# design.net
KiCad netlist of a schematic drawn in Altium Designer
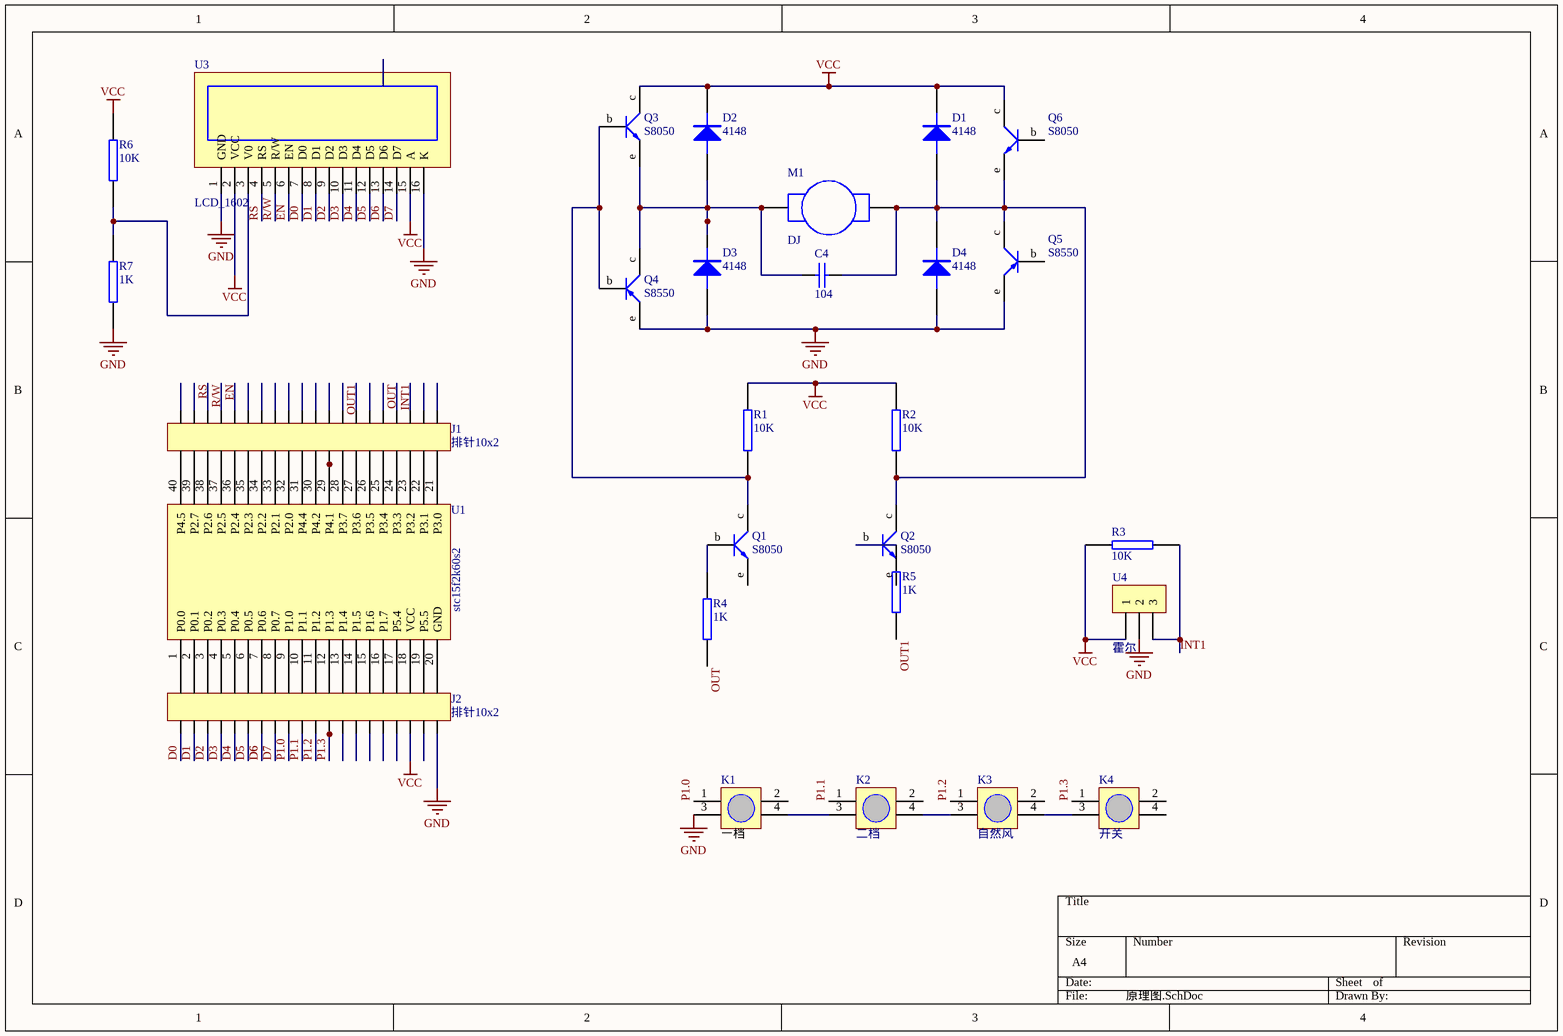
[diagram p0: 原理图.SchDoc]

(export (version "E")
  (design (tool "Eeschema 10.0.6"))
  (components
    (comp (ref "C4")
      (value "104")
      (footprint "C01")
      (description "Capacitor")
      (libsource (lib "altium-import") (part "root_1_CAP_"))
    )
    (comp (ref "D1")
      (value "4148")
      (footprint "DIODE0.2")
      (description "Diode")
      (libsource (lib "altium-import") (part "root_1_DIODE_"))
    )
    (comp (ref "D2")
      (value "4148")
      (footprint "DIODE0.2")
      (description "Diode")
      (libsource (lib "altium-import") (part "root_1_DIODE_"))
    )
    (comp (ref "D3")
      (value "4148")
      (footprint "DIODE0.2")
      (description "Diode")
      (libsource (lib "altium-import") (part "root_1_DIODE_"))
    )
    (comp (ref "D4")
      (value "4148")
      (footprint "DIODE0.2")
      (description "Diode")
      (libsource (lib "altium-import") (part "root_1_DIODE_"))
    )
    (comp (ref "J1") (value "排针10x2") (libsource (lib "原理图库") (part "排针10x2")))
    (comp (ref "J2") (value "排针10x2") (libsource (lib "原理图库") (part "排针10x2")))
    (comp (ref "K1") (value "一档") (footprint "KEY") (libsource (lib "altium-import") (part "root_0_KEY_")))
    (comp (ref "K2") (value "二档") (footprint "KEY") (libsource (lib "altium-import") (part "root_0_KEY_")))
    (comp (ref "K3") (value "自然风") (footprint "KEY") (libsource (lib "altium-import") (part "root_0_KEY_")))
    (comp (ref "K4") (value "开关") (footprint "KEY") (libsource (lib "altium-import") (part "root_0_KEY_")))
    (comp (ref "M1")
      (value "DJ")
      (footprint "SIP2")
      (libsource (lib "altium-import") (part "root_1_MOTOR AC_"))
    )
    (comp (ref "Q1") (value "S8050") (footprint "PNP") (libsource (lib "altium-import") (part "root_0_NPN_")))
    (comp (ref "Q2") (value "S8050") (footprint "PNP") (libsource (lib "altium-import") (part "root_0_NPN_")))
    (comp (ref "Q3") (value "S8050") (footprint "PNP") (libsource (lib "altium-import") (part "root_0_NPN_")))
    (comp (ref "Q4") (value "S8550") (footprint "PNP") (libsource (lib "altium-import") (part "root_0_PNP_")))
    (comp (ref "Q5")
      (value "S8550")
      (footprint "PNP")
      (libsource (lib "altium-import") (part "root_0_mirrored_PNP_"))
    )
    (comp (ref "Q6")
      (value "S8050")
      (footprint "PNP")
      (libsource (lib "altium-import") (part "root_0_mirrored_NPN_"))
    )
    (comp (ref "R1")
      (value "10K")
      (footprint "R-DIP")
      (libsource (lib "altium-import") (part "root_3_RES2_"))
    )
    (comp (ref "R2")
      (value "10K")
      (footprint "R-DIP")
      (libsource (lib "altium-import") (part "root_3_RES2_"))
    )
    (comp (ref "R3")
      (value "10K")
      (footprint "R-DIP")
      (libsource (lib "altium-import") (part "root_0_RES2_"))
    )
    (comp (ref "R4") (value "1K") (footprint "R-DIP") (libsource (lib "altium-import") (part "root_3_RES2_")))
    (comp (ref "R5") (value "1K") (footprint "R-DIP") (libsource (lib "altium-import") (part "root_3_RES2_")))
    (comp (ref "R6")
      (value "10K")
      (footprint "R-DIP")
      (libsource (lib "altium-import") (part "root_3_RES2_"))
    )
    (comp (ref "R7") (value "1K") (footprint "R-DIP") (libsource (lib "altium-import") (part "root_3_RES2_")))
    (comp (ref "U1") (value "stc15f2k60s2") (libsource (lib "altium-import") (part "root_1_STC15F2K60S2_")))
    (comp (ref "U3")
      (value "LCD_1602")
      (footprint "SIP16")
      (libsource (lib "altium-import") (part "root_0_mirrored_LCM1602_"))
    )
    (comp (ref "U4")
      (value "霍尔")
      (footprint "SIP3")
      (description "Connector")
      (libsource (lib "altium-import") (part "root_1_CON3_"))
    )
  )
  (nets
    (net (code "1") (name "/D0") (class "Default")
      (node (ref "J2") (pin "1") (pinfunction "1_1") (pintype "passive"))
      (node (ref "U3") (pin "7") (pinfunction "D0_7") (pintype "passive"))
    )
    (net (code "2") (name "/D1") (class "Default")
      (node (ref "J2") (pin "2") (pinfunction "2_2") (pintype "passive"))
      (node (ref "U3") (pin "8") (pinfunction "D1_8") (pintype "passive"))
    )
    (net (code "3") (name "/D2") (class "Default")
      (node (ref "J2") (pin "2") (pinfunction "2_2") (pintype "passive"))
      (node (ref "U3") (pin "9") (pinfunction "D2_9") (pintype "passive"))
    )
    (net (code "4") (name "/D3") (class "Default")
      (node (ref "J2") (pin "2") (pinfunction "2_2") (pintype "passive"))
      (node (ref "U3") (pin "10") (pinfunction "D3_10") (pintype "passive"))
    )
    (net (code "5") (name "/D4") (class "Default")
      (node (ref "J2") (pin "2") (pinfunction "2_2") (pintype "passive"))
      (node (ref "U3") (pin "11") (pinfunction "D4_11") (pintype "passive"))
    )
    (net (code "6") (name "/D5") (class "Default")
      (node (ref "J2") (pin "2") (pinfunction "2_2") (pintype "passive"))
      (node (ref "U3") (pin "12") (pinfunction "D5_12") (pintype "passive"))
    )
    (net (code "7") (name "/D6") (class "Default")
      (node (ref "J2") (pin "1") (pinfunction "1_1") (pintype "passive"))
      (node (ref "U3") (pin "13") (pinfunction "D6_13") (pintype "passive"))
    )
    (net (code "8") (name "/D7") (class "Default")
      (node (ref "J2") (pin "2") (pinfunction "2_2") (pintype "passive"))
      (node (ref "U3") (pin "14") (pinfunction "D7_14") (pintype "passive"))
    )
    (net (code "9") (name "/EN") (class "Default")
      (node (ref "J1") (pin "3") (pinfunction "3_3") (pintype "passive"))
      (node (ref "U3") (pin "6") (pinfunction "EN_6") (pintype "passive"))
    )
    (net (code "10") (name "/INT1") (class "Default")
      (node (ref "J1") (pin "3") (pinfunction "3_3") (pintype "passive"))
      (node (ref "R3") (pin "2") (pinfunction "2_2") (pintype "passive"))
      (node (ref "U4") (pin "3") (pinfunction "3_3") (pintype "passive"))
    )
    (net (code "11") (name "/OUT") (class "Default")
      (node (ref "J1") (pin "3") (pinfunction "3_3") (pintype "passive"))
      (node (ref "R4") (pin "2") (pinfunction "2_2") (pintype "passive"))
    )
    (net (code "12") (name "/OUT1") (class "Default")
      (node (ref "J1") (pin "2") (pinfunction "2_2") (pintype "passive"))
      (node (ref "R5") (pin "2") (pinfunction "2_2") (pintype "passive"))
    )
    (net (code "13") (name "/P1.0") (class "Default")
      (node (ref "J2") (pin "2") (pinfunction "2_2") (pintype "passive"))
      (node (ref "K1") (pin "1") (pintype "passive"))
    )
    (net (code "14") (name "/P1.1") (class "Default")
      (node (ref "J2") (pin "2") (pinfunction "2_2") (pintype "passive"))
      (node (ref "K2") (pin "1") (pintype "passive"))
    )
    (net (code "15") (name "/P1.2") (class "Default")
      (node (ref "J2") (pin "2") (pinfunction "2_2") (pintype "passive"))
      (node (ref "K3") (pin "1") (pintype "passive"))
    )
    (net (code "16") (name "/P1.3") (class "Default")
      (node (ref "J2") (pin "1") (pinfunction "1_1") (pintype "passive"))
      (node (ref "J2") (pin "2") (pinfunction "2_2") (pintype "passive"))
      (node (ref "K4") (pin "1") (pintype "passive"))
    )
    (net (code "17") (name "/RS") (class "Default")
      (node (ref "J1") (pin "3") (pinfunction "3_3") (pintype "passive"))
      (node (ref "U3") (pin "4") (pinfunction "RS_4") (pintype "passive"))
    )
    (net (code "18") (name "/R{slash}W") (class "Default")
      (node (ref "J1") (pin "2") (pinfunction "2_2") (pintype "passive"))
      (node (ref "U3") (pin "5") (pinfunction "R/W_5") (pintype "passive"))
    )
    (net (code "19") (name "GND") (class "Default")
      (node (ref "D3") (pin "1") (pinfunction "A_1") (pintype "passive"))
      (node (ref "D4") (pin "1") (pinfunction "A_1") (pintype "passive"))
      (node (ref "J2") (pin "2") (pinfunction "2_2") (pintype "passive"))
      (node (ref "K1") (pin "3") (pintype "passive"))
      (node (ref "Q4") (pin "e") (pintype "passive"))
      (node (ref "Q5") (pin "e") (pintype "passive"))
      (node (ref "R7") (pin "2") (pinfunction "2_2") (pintype "passive"))
      (node (ref "U3") (pin "1") (pinfunction "GND_1") (pintype "passive"))
      (node (ref "U3") (pin "16") (pinfunction "K_16") (pintype "passive"))
      (node (ref "U4") (pin "2") (pinfunction "2_2") (pintype "passive"))
    )
    (net (code "20") (name "Net-(D1-A)") (class "Default")
      (node (ref "C4") (pin "2") (pinfunction "2_2") (pintype "passive"))
      (node (ref "D1") (pin "1") (pinfunction "A_1") (pintype "passive"))
      (node (ref "D4") (pin "2") (pinfunction "K_2") (pintype "passive"))
      (node (ref "M1") (pin "2") (pinfunction "2_2") (pintype "passive"))
      (node (ref "Q2") (pin "c") (pintype "passive"))
      (node (ref "Q5") (pin "c") (pintype "passive"))
      (node (ref "Q6") (pin "e") (pintype "passive"))
      (node (ref "R2") (pin "2") (pinfunction "2_2") (pintype "passive"))
    )
    (net (code "21") (name "Net-(D2-A)") (class "Default")
      (node (ref "C4") (pin "1") (pinfunction "1_1") (pintype "passive"))
      (node (ref "D2") (pin "1") (pinfunction "A_1") (pintype "passive"))
      (node (ref "D3") (pin "2") (pinfunction "K_2") (pintype "passive"))
      (node (ref "M1") (pin "1") (pinfunction "1_1") (pintype "passive"))
      (node (ref "Q3") (pin "e") (pintype "passive"))
      (node (ref "Q4") (pin "c") (pintype "passive"))
    )
    (net (code "22") (name "Net-(K1-Pad4)") (class "Default")
      (node (ref "K1") (pin "4") (pintype "passive"))
      (node (ref "K2") (pin "3") (pintype "passive"))
    )
    (net (code "23") (name "Net-(K2-Pad4)") (class "Default")
      (node (ref "K2") (pin "4") (pintype "passive"))
      (node (ref "K3") (pin "3") (pintype "passive"))
    )
    (net (code "24") (name "Net-(K3-Pad4)") (class "Default")
      (node (ref "K3") (pin "4") (pintype "passive"))
      (node (ref "K4") (pin "3") (pintype "passive"))
    )
    (net (code "25") (name "Net-(Q1-Padb)") (class "Default")
      (node (ref "Q1") (pin "b") (pintype "passive"))
      (node (ref "R4") (pin "1") (pinfunction "1_1") (pintype "passive"))
    )
    (net (code "26") (name "Net-(Q1-Padc)") (class "Default")
      (node (ref "Q1") (pin "c") (pintype "passive"))
      (node (ref "Q3") (pin "b") (pintype "passive"))
      (node (ref "Q4") (pin "b") (pintype "passive"))
      (node (ref "R1") (pin "2") (pinfunction "2_2") (pintype "passive"))
    )
    (net (code "27") (name "Net-(Q2-Padb)") (class "Default")
      (node (ref "Q2") (pin "b") (pintype "passive"))
      (node (ref "R5") (pin "1") (pinfunction "1_1") (pintype "passive"))
    )
    (net (code "28") (name "Net-(U1-GND)") (class "Default")
      (node (ref "J2") (pin "2") (pinfunction "2_2") (pintype "passive"))
      (node (ref "U1") (pin "20") (pinfunction "GND_20") (pintype "passive"))
    )
    (net (code "29") (name "Net-(U1-P0.0)") (class "Default")
      (node (ref "J2") (pin "2") (pinfunction "2_2") (pintype "passive"))
      (node (ref "U1") (pin "1") (pinfunction "P0.0_1") (pintype "passive"))
    )
    (net (code "30") (name "Net-(U1-P0.1)") (class "Default")
      (node (ref "J2") (pin "3") (pinfunction "3_3") (pintype "passive"))
      (node (ref "U1") (pin "2") (pinfunction "P0.1_2") (pintype "passive"))
    )
    (net (code "31") (name "Net-(U1-P0.2)") (class "Default")
      (node (ref "J2") (pin "2") (pinfunction "2_2") (pintype "passive"))
      (node (ref "U1") (pin "3") (pinfunction "P0.2_3") (pintype "passive"))
    )
    (net (code "32") (name "Net-(U1-P0.3)") (class "Default")
      (node (ref "J2") (pin "3") (pinfunction "3_3") (pintype "passive"))
      (node (ref "U1") (pin "4") (pinfunction "P0.3_4") (pintype "passive"))
    )
    (net (code "33") (name "Net-(U1-P0.4)") (class "Default")
      (node (ref "J2") (pin "2") (pinfunction "2_2") (pintype "passive"))
      (node (ref "U1") (pin "5") (pinfunction "P0.4_5") (pintype "passive"))
    )
    (net (code "34") (name "Net-(U1-P0.5)") (class "Default")
      (node (ref "J2") (pin "3") (pinfunction "3_3") (pintype "passive"))
      (node (ref "U1") (pin "6") (pinfunction "P0.5_6") (pintype "passive"))
    )
    (net (code "35") (name "Net-(U1-P0.6)") (class "Default")
      (node (ref "J2") (pin "2") (pinfunction "2_2") (pintype "passive"))
      (node (ref "U1") (pin "7") (pinfunction "P0.6_7") (pintype "passive"))
    )
    (net (code "36") (name "Net-(U1-P0.7)") (class "Default")
      (node (ref "J2") (pin "3") (pinfunction "3_3") (pintype "passive"))
      (node (ref "U1") (pin "8") (pinfunction "P0.7_8") (pintype "passive"))
    )
    (net (code "37") (name "Net-(U1-P1.0)") (class "Default")
      (node (ref "J2") (pin "2") (pinfunction "2_2") (pintype "passive"))
      (node (ref "U1") (pin "9") (pinfunction "P1.0_9") (pintype "passive"))
    )
    (net (code "38") (name "Net-(U1-P1.1)") (class "Default")
      (node (ref "J2") (pin "3") (pinfunction "3_3") (pintype "passive"))
      (node (ref "U1") (pin "10") (pinfunction "P1.1_10") (pintype "passive"))
    )
    (net (code "39") (name "Net-(U1-P1.2)") (class "Default")
      (node (ref "J2") (pin "2") (pinfunction "2_2") (pintype "passive"))
      (node (ref "U1") (pin "11") (pinfunction "P1.2_11") (pintype "passive"))
    )
    (net (code "40") (name "Net-(U1-P1.3)") (class "Default")
      (node (ref "J2") (pin "3") (pinfunction "3_3") (pintype "passive"))
      (node (ref "U1") (pin "12") (pinfunction "P1.3_12") (pintype "passive"))
    )
    (net (code "41") (name "Net-(U1-P1.4)") (class "Default")
      (node (ref "J2") (pin "2") (pinfunction "2_2") (pintype "passive"))
      (node (ref "U1") (pin "13") (pinfunction "P1.4_13") (pintype "passive"))
    )
    (net (code "42") (name "Net-(U1-P1.5)") (class "Default")
      (node (ref "J2") (pin "3") (pinfunction "3_3") (pintype "passive"))
      (node (ref "U1") (pin "14") (pinfunction "P1.5_14") (pintype "passive"))
    )
    (net (code "43") (name "Net-(U1-P1.6)") (class "Default")
      (node (ref "J2") (pin "2") (pinfunction "2_2") (pintype "passive"))
      (node (ref "U1") (pin "15") (pinfunction "P1.6_15") (pintype "passive"))
    )
    (net (code "44") (name "Net-(U1-P1.7)") (class "Default")
      (node (ref "J2") (pin "3") (pinfunction "3_3") (pintype "passive"))
      (node (ref "U1") (pin "16") (pinfunction "P1.7_16") (pintype "passive"))
    )
    (net (code "45") (name "Net-(U1-P2.0)") (class "Default")
      (node (ref "J1") (pin "2") (pinfunction "2_2") (pintype "passive"))
      (node (ref "U1") (pin "32") (pinfunction "P2.0_32") (pintype "passive"))
    )
    (net (code "46") (name "Net-(U1-P2.1)") (class "Default")
      (node (ref "J1") (pin "2") (pinfunction "2_2") (pintype "passive"))
      (node (ref "U1") (pin "33") (pinfunction "P2.1_33") (pintype "passive"))
    )
    (net (code "47") (name "Net-(U1-P2.2)") (class "Default")
      (node (ref "J1") (pin "1") (pinfunction "1_1") (pintype "passive"))
      (node (ref "U1") (pin "34") (pinfunction "P2.2_34") (pintype "passive"))
    )
    (net (code "48") (name "Net-(U1-P2.3)") (class "Default")
      (node (ref "J1") (pin "2") (pinfunction "2_2") (pintype "passive"))
      (node (ref "U1") (pin "35") (pinfunction "P2.3_35") (pintype "passive"))
    )
    (net (code "49") (name "Net-(U1-P2.4)") (class "Default")
      (node (ref "J1") (pin "2") (pinfunction "2_2") (pintype "passive"))
      (node (ref "U1") (pin "36") (pinfunction "P2.4_36") (pintype "passive"))
    )
    (net (code "50") (name "Net-(U1-P2.5)") (class "Default")
      (node (ref "J1") (pin "2") (pinfunction "2_2") (pintype "passive"))
      (node (ref "U1") (pin "37") (pinfunction "P2.5_37") (pintype "passive"))
    )
    (net (code "51") (name "Net-(U1-P2.6)") (class "Default")
      (node (ref "J1") (pin "2") (pinfunction "2_2") (pintype "passive"))
      (node (ref "U1") (pin "38") (pinfunction "P2.6_38") (pintype "passive"))
    )
    (net (code "52") (name "Net-(U1-P2.7)") (class "Default")
      (node (ref "J1") (pin "2") (pinfunction "2_2") (pintype "passive"))
      (node (ref "U1") (pin "39") (pinfunction "P2.7_39") (pintype "passive"))
    )
    (net (code "53") (name "Net-(U1-P3.0)") (class "Default")
      (node (ref "J1") (pin "2") (pinfunction "2_2") (pintype "passive"))
      (node (ref "U1") (pin "21") (pinfunction "P3.0_21") (pintype "passive"))
    )
    (net (code "54") (name "Net-(U1-P3.1)") (class "Default")
      (node (ref "J1") (pin "2") (pinfunction "2_2") (pintype "passive"))
      (node (ref "U1") (pin "22") (pinfunction "P3.1_22") (pintype "passive"))
    )
    (net (code "55") (name "Net-(U1-P3.2)") (class "Default")
      (node (ref "J1") (pin "1") (pinfunction "1_1") (pintype "passive"))
      (node (ref "U1") (pin "23") (pinfunction "P3.2_23") (pintype "passive"))
    )
    (net (code "56") (name "Net-(U1-P3.3)") (class "Default")
      (node (ref "J1") (pin "2") (pinfunction "2_2") (pintype "passive"))
      (node (ref "U1") (pin "24") (pinfunction "P3.3_24") (pintype "passive"))
    )
    (net (code "57") (name "Net-(U1-P3.4)") (class "Default")
      (node (ref "J1") (pin "2") (pinfunction "2_2") (pintype "passive"))
      (node (ref "U1") (pin "25") (pinfunction "P3.4_25") (pintype "passive"))
    )
    (net (code "58") (name "Net-(U1-P3.5)") (class "Default")
      (node (ref "J1") (pin "2") (pinfunction "2_2") (pintype "passive"))
      (node (ref "U1") (pin "26") (pinfunction "P3.5_26") (pintype "passive"))
    )
    (net (code "59") (name "Net-(U1-P3.6)") (class "Default")
      (node (ref "J1") (pin "2") (pinfunction "2_2") (pintype "passive"))
      (node (ref "U1") (pin "27") (pinfunction "P3.6_27") (pintype "passive"))
    )
    (net (code "60") (name "Net-(U1-P3.7)") (class "Default")
      (node (ref "J1") (pin "2") (pinfunction "2_2") (pintype "passive"))
      (node (ref "U1") (pin "28") (pinfunction "P3.7_28") (pintype "passive"))
    )
    (net (code "61") (name "Net-(U1-P4.1)") (class "Default")
      (node (ref "J1") (pin "1") (pinfunction "1_1") (pintype "passive"))
      (node (ref "J1") (pin "2") (pinfunction "2_2") (pintype "passive"))
      (node (ref "U1") (pin "29") (pinfunction "P4.1_29") (pintype "passive"))
    )
    (net (code "62") (name "Net-(U1-P4.2)") (class "Default")
      (node (ref "J1") (pin "2") (pinfunction "2_2") (pintype "passive"))
      (node (ref "U1") (pin "30") (pinfunction "P4.2_30") (pintype "passive"))
    )
    (net (code "63") (name "Net-(U1-P4.4)") (class "Default")
      (node (ref "J1") (pin "2") (pinfunction "2_2") (pintype "passive"))
      (node (ref "U1") (pin "31") (pinfunction "P4.4_31") (pintype "passive"))
    )
    (net (code "64") (name "Net-(U1-P4.5)") (class "Default")
      (node (ref "J1") (pin "1") (pinfunction "1_1") (pintype "passive"))
      (node (ref "U1") (pin "40") (pinfunction "P4.5_40") (pintype "passive"))
    )
    (net (code "65") (name "Net-(U1-P5.4)") (class "Default")
      (node (ref "J2") (pin "3") (pinfunction "3_3") (pintype "passive"))
      (node (ref "U1") (pin "17") (pinfunction "P5.4_17") (pintype "passive"))
    )
    (net (code "66") (name "Net-(U1-P5.5)") (class "Default")
      (node (ref "J2") (pin "3") (pinfunction "3_3") (pintype "passive"))
      (node (ref "U1") (pin "19") (pinfunction "P5.5_19") (pintype "passive"))
    )
    (net (code "67") (name "Net-(U1-VCC)") (class "Default")
      (node (ref "J2") (pin "2") (pinfunction "2_2") (pintype "passive"))
      (node (ref "U1") (pin "18") (pinfunction "VCC_18") (pintype "passive"))
    )
    (net (code "68") (name "Net-(U3-V0)") (class "Default")
      (node (ref "R6") (pin "2") (pinfunction "2_2") (pintype "passive"))
      (node (ref "R7") (pin "1") (pinfunction "1_1") (pintype "passive"))
      (node (ref "U3") (pin "3") (pinfunction "V0_3") (pintype "passive"))
    )
    (net (code "69") (name "VCC") (class "Default")
      (node (ref "D1") (pin "2") (pinfunction "K_2") (pintype "passive"))
      (node (ref "D2") (pin "2") (pinfunction "K_2") (pintype "passive"))
      (node (ref "J2") (pin "1") (pinfunction "1_1") (pintype "passive"))
      (node (ref "Q3") (pin "c") (pintype "passive"))
      (node (ref "Q6") (pin "c") (pintype "passive"))
      (node (ref "R1") (pin "1") (pinfunction "1_1") (pintype "passive"))
      (node (ref "R2") (pin "1") (pinfunction "1_1") (pintype "passive"))
      (node (ref "R3") (pin "1") (pinfunction "1_1") (pintype "passive"))
      (node (ref "R6") (pin "1") (pinfunction "1_1") (pintype "passive"))
      (node (ref "U3") (pin "15") (pinfunction "A_15") (pintype "passive"))
      (node (ref "U3") (pin "2") (pinfunction "VCC_2") (pintype "passive"))
      (node (ref "U4") (pin "1") (pinfunction "1_1") (pintype "passive"))
    )
    (net (code "70") (name "unconnected-(J1-Pad2)") (class "Default")
      (node (ref "J1") (pin "2") (pinfunction "2_2") (pintype "passive"))
    )
    (net (code "71") (name "unconnected-(J1-Pad2)_1") (class "Default")
      (node (ref "J1") (pin "2") (pinfunction "2_2") (pintype "passive"))
    )
    (net (code "72") (name "unconnected-(J1-Pad2)_2") (class "Default")
      (node (ref "J1") (pin "2") (pinfunction "2_2") (pintype "passive"))
    )
    (net (code "73") (name "unconnected-(J1-Pad2)_3") (class "Default")
      (node (ref "J1") (pin "2") (pinfunction "2_2") (pintype "passive"))
    )
    (net (code "74") (name "unconnected-(J1-Pad2)_4") (class "Default")
      (node (ref "J1") (pin "2") (pinfunction "2_2") (pintype "passive"))
    )
    (net (code "75") (name "unconnected-(J1-Pad2)_5") (class "Default")
      (node (ref "J1") (pin "2") (pinfunction "2_2") (pintype "passive"))
    )
    (net (code "76") (name "unconnected-(J1-Pad2)_6") (class "Default")
      (node (ref "J1") (pin "2") (pinfunction "2_2") (pintype "passive"))
    )
    (net (code "77") (name "unconnected-(J1-Pad2)_7") (class "Default")
      (node (ref "J1") (pin "2") (pinfunction "2_2") (pintype "passive"))
    )
    (net (code "78") (name "unconnected-(J1-Pad3)") (class "Default")
      (node (ref "J1") (pin "3") (pinfunction "3_3") (pintype "passive"))
    )
    (net (code "79") (name "unconnected-(J1-Pad3)_1") (class "Default")
      (node (ref "J1") (pin "3") (pinfunction "3_3") (pintype "passive"))
    )
    (net (code "80") (name "unconnected-(J1-Pad3)_2") (class "Default")
      (node (ref "J1") (pin "3") (pinfunction "3_3") (pintype "passive"))
    )
    (net (code "81") (name "unconnected-(J1-Pad3)_3") (class "Default")
      (node (ref "J1") (pin "3") (pinfunction "3_3") (pintype "passive"))
    )
    (net (code "82") (name "unconnected-(J1-Pad3)_4") (class "Default")
      (node (ref "J1") (pin "3") (pinfunction "3_3") (pintype "passive"))
    )
    (net (code "83") (name "unconnected-(J1-Pad3)_5") (class "Default")
      (node (ref "J1") (pin "3") (pinfunction "3_3") (pintype "passive"))
    )
    (net (code "84") (name "unconnected-(J2-Pad2)") (class "Default")
      (node (ref "J2") (pin "2") (pinfunction "2_2") (pintype "passive"))
    )
    (net (code "85") (name "unconnected-(J2-Pad2)_1") (class "Default")
      (node (ref "J2") (pin "2") (pinfunction "2_2") (pintype "passive"))
    )
    (net (code "86") (name "unconnected-(J2-Pad2)_2") (class "Default")
      (node (ref "J2") (pin "2") (pinfunction "2_2") (pintype "passive"))
    )
    (net (code "87") (name "unconnected-(J2-Pad2)_3") (class "Default")
      (node (ref "J2") (pin "2") (pinfunction "2_2") (pintype "passive"))
    )
    (net (code "88") (name "unconnected-(J2-Pad2)_4") (class "Default")
      (node (ref "J2") (pin "2") (pinfunction "2_2") (pintype "passive"))
    )
    (net (code "89") (name "unconnected-(J2-Pad2)_5") (class "Default")
      (node (ref "J2") (pin "2") (pinfunction "2_2") (pintype "passive"))
    )
    (net (code "90") (name "unconnected-(K1-Pad2)") (class "Default")
      (node (ref "K1") (pin "2") (pintype "passive"))
    )
    (net (code "91") (name "unconnected-(K2-Pad2)") (class "Default")
      (node (ref "K2") (pin "2") (pintype "passive"))
    )
    (net (code "92") (name "unconnected-(K3-Pad2)") (class "Default")
      (node (ref "K3") (pin "2") (pintype "passive"))
    )
    (net (code "93") (name "unconnected-(K4-Pad2)") (class "Default")
      (node (ref "K4") (pin "2") (pintype "passive"))
    )
    (net (code "94") (name "unconnected-(K4-Pad4)") (class "Default")
      (node (ref "K4") (pin "4") (pintype "passive"))
    )
    (net (code "95") (name "unconnected-(Q1-Pade)") (class "Default")
      (node (ref "Q1") (pin "e") (pintype "passive"))
    )
    (net (code "96") (name "unconnected-(Q2-Pade)") (class "Default")
      (node (ref "Q2") (pin "e") (pintype "passive"))
    )
    (net (code "97") (name "unconnected-(Q5-Padb)") (class "Default")
      (node (ref "Q5") (pin "b") (pintype "passive"))
    )
    (net (code "98") (name "unconnected-(Q6-Padb)") (class "Default")
      (node (ref "Q6") (pin "b") (pintype "passive"))
    )
  )
)
